# NeuroMIX.net
KiCad netlist of a schematic drawn in Altium Designer
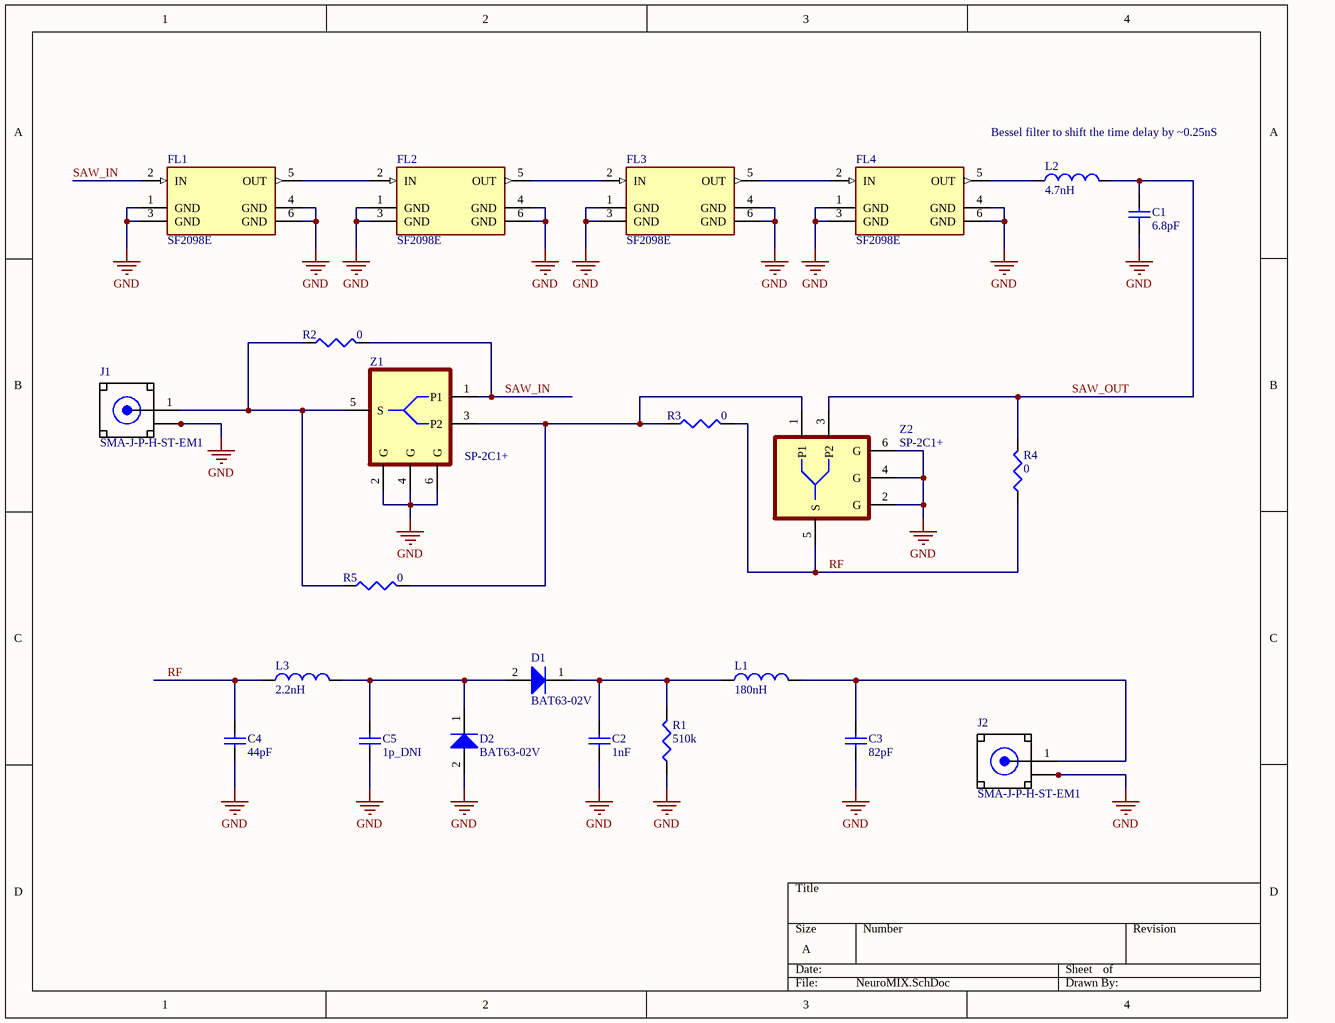
[diagram p0: NeuroMIX.SchDoc]

(export (version "E")
  (design (tool "Eeschema 10.0.6"))
  (components
    (comp (ref "C1")
      (value "6.8pF")
      (footprint "SMD-0603")
      (description "Ceramic Capacitor 0603")
      (libsource (lib "LCR") (part "CAP0603"))
    )
    (comp (ref "C2")
      (value "1nF")
      (footprint "SMD-0603")
      (description "Ceramic Capacitor 0603")
      (libsource (lib "LCR") (part "CAP0603"))
    )
    (comp (ref "C3")
      (value "82pF")
      (footprint "SMD-0603")
      (description "Ceramic Capacitor 0603")
      (libsource (lib "LCR") (part "CAP0603"))
    )
    (comp (ref "C4")
      (value "44pF")
      (footprint "SMD-0603")
      (description "Ceramic Capacitor 0603")
      (libsource (lib "LCR") (part "CAP0603"))
    )
    (comp (ref "C5")
      (value "1p_DNI")
      (footprint "SMD-0603")
      (description "Ceramic Capacitor 0603")
      (libsource (lib "LCR") (part "CAP0603"))
    )
    (comp (ref "D1")
      (value "BAT63-02V")
      (footprint "INF-SC79_V")
      (description "Single Silicon Schottky Diode, 100 mA IF Max, SC79, Green")
      (fields (field (name "MANUFACTURER") "Infineon"))
      (libsource (lib "BAT63-02V") (part "BAT63-02V"))
    )
    (comp (ref "D2")
      (value "BAT63-02V")
      (footprint "INF-SC79_V")
      (description "Single Silicon Schottky Diode, 100 mA IF Max, SC79, Green")
      (fields (field (name "MANUFACTURER") "Infineon"))
      (libsource (lib "BAT63-02V") (part "BAT63-02V"))
    )
    (comp (ref "FL1")
      (value "SF2098E")
      (footprint "FIL_SF2098E")
      (description "915MHz Frequency Wireless RF SAW Filter (Sound Acoustic Wave) 1.9dB 26MHz Bandwidth 6-SMD, No Lead")
      (fields (field (name "MF") "Murata Electronics"))
      (libsource (lib "saw") (part "SF2098E"))
    )
    (comp (ref "FL2")
      (value "SF2098E")
      (footprint "FIL_SF2098E")
      (description "915MHz Frequency Wireless RF SAW Filter (Sound Acoustic Wave) 1.9dB 26MHz Bandwidth 6-SMD, No Lead")
      (fields (field (name "MF") "Murata Electronics"))
      (libsource (lib "saw") (part "SF2098E"))
    )
    (comp (ref "FL3")
      (value "SF2098E")
      (footprint "FIL_SF2098E")
      (description "915MHz Frequency Wireless RF SAW Filter (Sound Acoustic Wave) 1.9dB 26MHz Bandwidth 6-SMD, No Lead")
      (fields (field (name "MF") "Murata Electronics"))
      (libsource (lib "saw") (part "SF2098E"))
    )
    (comp (ref "FL4")
      (value "SF2098E")
      (footprint "FIL_SF2098E")
      (description "915MHz Frequency Wireless RF SAW Filter (Sound Acoustic Wave) 1.9dB 26MHz Bandwidth 6-SMD, No Lead")
      (fields (field (name "MF") "Murata Electronics"))
      (libsource (lib "saw") (part "SF2098E"))
    )
    (comp (ref "J1")
      (value "SMA-J-P-H-ST-EM1")
      (footprint "SMA-J-P-H-ST-EM1")
      (description "Connector SMA F 50Ohm Solder ST Edge Mount Gold Over Nickel Tray")
      (fields (field (name "MF") "Samtec"))
      (libsource (lib "Connectors") (part "SMA-J-P-H-ST-EM1"))
    )
    (comp (ref "J2")
      (value "SMA-J-P-H-ST-EM1")
      (footprint "SMA-J-P-H-ST-EM1")
      (description "Connector SMA F 50Ohm Solder ST Edge Mount Gold Over Nickel Tray")
      (fields (field (name "MF") "Samtec"))
      (libsource (lib "Connectors") (part "SMA-J-P-H-ST-EM1"))
    )
    (comp (ref "L1")
      (value "180nH")
      (footprint "SMD-0603")
      (description "Inductor 0603")
      (libsource (lib "LCR") (part "L0603"))
    )
    (comp (ref "L2")
      (value "4.7nH")
      (footprint "SMD-0603")
      (description "Inductor 0603")
      (libsource (lib "LCR") (part "L0603"))
    )
    (comp (ref "L3")
      (value "2.2nH")
      (footprint "SMD-0603")
      (description "Inductor 0603")
      (libsource (lib "LCR") (part "L0603"))
    )
    (comp (ref "R1")
      (value "510k")
      (footprint "SMD-0603")
      (description "Resistor-0603")
      (libsource (lib "LCR") (part "RES0603"))
    )
    (comp (ref "R2")
      (value "0")
      (footprint "SMD-0603")
      (description "Resistor-0603")
      (libsource (lib "LCR") (part "RES0603"))
    )
    (comp (ref "R3")
      (value "0")
      (footprint "SMD-0603")
      (description "Resistor-0603")
      (libsource (lib "LCR") (part "RES0603"))
    )
    (comp (ref "R4")
      (value "0")
      (footprint "SMD-0603")
      (description "Resistor-0603")
      (libsource (lib "LCR") (part "RES0603"))
    )
    (comp (ref "R5")
      (value "0")
      (footprint "SMD-0603")
      (description "Resistor-0603")
      (libsource (lib "LCR") (part "RES0603"))
    )
    (comp (ref "Z1")
      (value "SP-2C1+")
      (footprint "SP-2C1+")
      (description "Power Divider, 2 Way-0 , 640 to 1100MHz, 50 ohms, SMT")
      (fields (field (name "MF") "Mini-Circuits") (field (name "MP") "SBTC-2-10L+"))
      (libsource (lib "Splitter") (part "SP-2C1+"))
    )
    (comp (ref "Z2")
      (value "SP-2C1+")
      (footprint "SP-2C1+")
      (description "Power Divider, 2 Way-0 , 640 to 1100MHz, 50 ohms, SMT")
      (fields (field (name "MF") "Mini-Circuits") (field (name "MP") "SBTC-2-10L+"))
      (libsource (lib "") (part "SP-2C1+_1"))
    )
  )
  (nets
    (net (code "1") (name "/RF") (class "Default")
      (node (ref "C4") (pin "2") (pinfunction "2_2") (pintype "passive"))
      (node (ref "L3") (pin "1") (pinfunction "1_1") (pintype "passive"))
      (node (ref "R3") (pin "2") (pinfunction "2_2") (pintype "passive"))
      (node (ref "R4") (pin "1") (pinfunction "1_1") (pintype "passive"))
      (node (ref "Z2") (pin "5") (pinfunction "S_5") (pintype "passive"))
    )
    (net (code "2") (name "/SAW_IN") (class "Default")
      (node (ref "FL1") (pin "2") (pinfunction "IN_2") (pintype "input"))
      (node (ref "R2") (pin "2") (pinfunction "2_2") (pintype "passive"))
      (node (ref "Z1") (pin "1") (pinfunction "P1_1") (pintype "passive"))
    )
    (net (code "3") (name "/SAW_OUT") (class "Default")
      (node (ref "C1") (pin "2") (pinfunction "2_2") (pintype "passive"))
      (node (ref "L2") (pin "2") (pinfunction "2_2") (pintype "passive"))
      (node (ref "R4") (pin "2") (pinfunction "2_2") (pintype "passive"))
      (node (ref "Z2") (pin "3") (pinfunction "P2_3") (pintype "passive"))
    )
    (net (code "4") (name "GND") (class "Default")
      (node (ref "C1") (pin "1") (pinfunction "1_1") (pintype "passive"))
      (node (ref "C2") (pin "1") (pinfunction "1_1") (pintype "passive"))
      (node (ref "C3") (pin "1") (pinfunction "1_1") (pintype "passive"))
      (node (ref "C4") (pin "1") (pinfunction "1_1") (pintype "passive"))
      (node (ref "C5") (pin "1") (pinfunction "1_1") (pintype "passive"))
      (node (ref "D2") (pin "2") (pinfunction "A_2") (pintype "passive"))
      (node (ref "FL1") (pin "1") (pinfunction "GND_1") (pintype "power_in"))
      (node (ref "FL1") (pin "3") (pinfunction "GND_3") (pintype "power_in"))
      (node (ref "FL1") (pin "4") (pinfunction "GND_4") (pintype "power_in"))
      (node (ref "FL1") (pin "6") (pinfunction "GND_6") (pintype "power_in"))
      (node (ref "FL2") (pin "1") (pinfunction "GND_1") (pintype "power_in"))
      (node (ref "FL2") (pin "3") (pinfunction "GND_3") (pintype "power_in"))
      (node (ref "FL2") (pin "4") (pinfunction "GND_4") (pintype "power_in"))
      (node (ref "FL2") (pin "6") (pinfunction "GND_6") (pintype "power_in"))
      (node (ref "FL3") (pin "1") (pinfunction "GND_1") (pintype "power_in"))
      (node (ref "FL3") (pin "3") (pinfunction "GND_3") (pintype "power_in"))
      (node (ref "FL3") (pin "4") (pinfunction "GND_4") (pintype "power_in"))
      (node (ref "FL3") (pin "6") (pinfunction "GND_6") (pintype "power_in"))
      (node (ref "FL4") (pin "1") (pinfunction "GND_1") (pintype "power_in"))
      (node (ref "FL4") (pin "3") (pinfunction "GND_3") (pintype "power_in"))
      (node (ref "FL4") (pin "4") (pinfunction "GND_4") (pintype "power_in"))
      (node (ref "FL4") (pin "6") (pinfunction "GND_6") (pintype "power_in"))
      (node (ref "J1") (pin "2_1") (pinfunction "GND_2_1") (pintype "power_in"))
      (node (ref "J1") (pin "2_2") (pinfunction "GND_2_2") (pintype "power_in"))
      (node (ref "J1") (pin "3_1") (pinfunction "GND_3_1") (pintype "power_in"))
      (node (ref "J1") (pin "3_2") (pinfunction "GND_3_2") (pintype "power_in"))
      (node (ref "J2") (pin "2_1") (pinfunction "GND_2_1") (pintype "power_in"))
      (node (ref "J2") (pin "2_2") (pinfunction "GND_2_2") (pintype "power_in"))
      (node (ref "J2") (pin "3_1") (pinfunction "GND_3_1") (pintype "power_in"))
      (node (ref "J2") (pin "3_2") (pinfunction "GND_3_2") (pintype "power_in"))
      (node (ref "R1") (pin "1") (pinfunction "1_1") (pintype "passive"))
      (node (ref "Z1") (pin "2") (pinfunction "G_2") (pintype "passive"))
      (node (ref "Z1") (pin "4") (pinfunction "G_4") (pintype "passive"))
      (node (ref "Z1") (pin "6") (pinfunction "G_6") (pintype "passive"))
      (node (ref "Z2") (pin "2") (pinfunction "G_2") (pintype "passive"))
      (node (ref "Z2") (pin "4") (pinfunction "G_4") (pintype "passive"))
      (node (ref "Z2") (pin "6") (pinfunction "G_6") (pintype "passive"))
    )
    (net (code "5") (name "Net-(D1-A)") (class "Default")
      (node (ref "C5") (pin "2") (pinfunction "2_2") (pintype "passive"))
      (node (ref "D1") (pin "2") (pinfunction "A_2") (pintype "passive"))
      (node (ref "D2") (pin "1") (pinfunction "K_1") (pintype "passive"))
      (node (ref "L3") (pin "2") (pinfunction "2_2") (pintype "passive"))
    )
    (net (code "6") (name "Net-(D1-K)") (class "Default")
      (node (ref "C2") (pin "2") (pinfunction "2_2") (pintype "passive"))
      (node (ref "D1") (pin "1") (pinfunction "K_1") (pintype "passive"))
      (node (ref "L1") (pin "1") (pinfunction "1_1") (pintype "passive"))
      (node (ref "R1") (pin "2") (pinfunction "2_2") (pintype "passive"))
    )
    (net (code "7") (name "Net-(FL1-OUT)") (class "Default")
      (node (ref "FL1") (pin "5") (pinfunction "OUT_5") (pintype "output"))
      (node (ref "FL2") (pin "2") (pinfunction "IN_2") (pintype "input"))
    )
    (net (code "8") (name "Net-(FL2-OUT)") (class "Default")
      (node (ref "FL2") (pin "5") (pinfunction "OUT_5") (pintype "output"))
      (node (ref "FL3") (pin "2") (pinfunction "IN_2") (pintype "input"))
    )
    (net (code "9") (name "Net-(FL3-OUT)") (class "Default")
      (node (ref "FL3") (pin "5") (pinfunction "OUT_5") (pintype "output"))
      (node (ref "FL4") (pin "2") (pinfunction "IN_2") (pintype "input"))
    )
    (net (code "10") (name "Net-(FL4-OUT)") (class "Default")
      (node (ref "FL4") (pin "5") (pinfunction "OUT_5") (pintype "output"))
      (node (ref "L2") (pin "1") (pinfunction "1_1") (pintype "passive"))
    )
    (net (code "11") (name "Net-(J1-SIGNAL)") (class "Default")
      (node (ref "J1") (pin "1") (pinfunction "SIGNAL_1") (pintype "passive"))
      (node (ref "R2") (pin "1") (pinfunction "1_1") (pintype "passive"))
      (node (ref "R5") (pin "1") (pinfunction "1_1") (pintype "passive"))
      (node (ref "Z1") (pin "5") (pinfunction "S_5") (pintype "passive"))
    )
    (net (code "12") (name "Net-(J2-SIGNAL)") (class "Default")
      (node (ref "C3") (pin "2") (pinfunction "2_2") (pintype "passive"))
      (node (ref "J2") (pin "1") (pinfunction "SIGNAL_1") (pintype "passive"))
      (node (ref "L1") (pin "2") (pinfunction "2_2") (pintype "passive"))
    )
    (net (code "13") (name "Net-(Z1-P2)") (class "Default")
      (node (ref "R3") (pin "1") (pinfunction "1_1") (pintype "passive"))
      (node (ref "R5") (pin "2") (pinfunction "2_2") (pintype "passive"))
      (node (ref "Z1") (pin "3") (pinfunction "P2_3") (pintype "passive"))
      (node (ref "Z2") (pin "1") (pinfunction "P1_1") (pintype "passive"))
    )
  )
)
